# schema.net
KiCad netlist of a schematic drawn in EAGLE
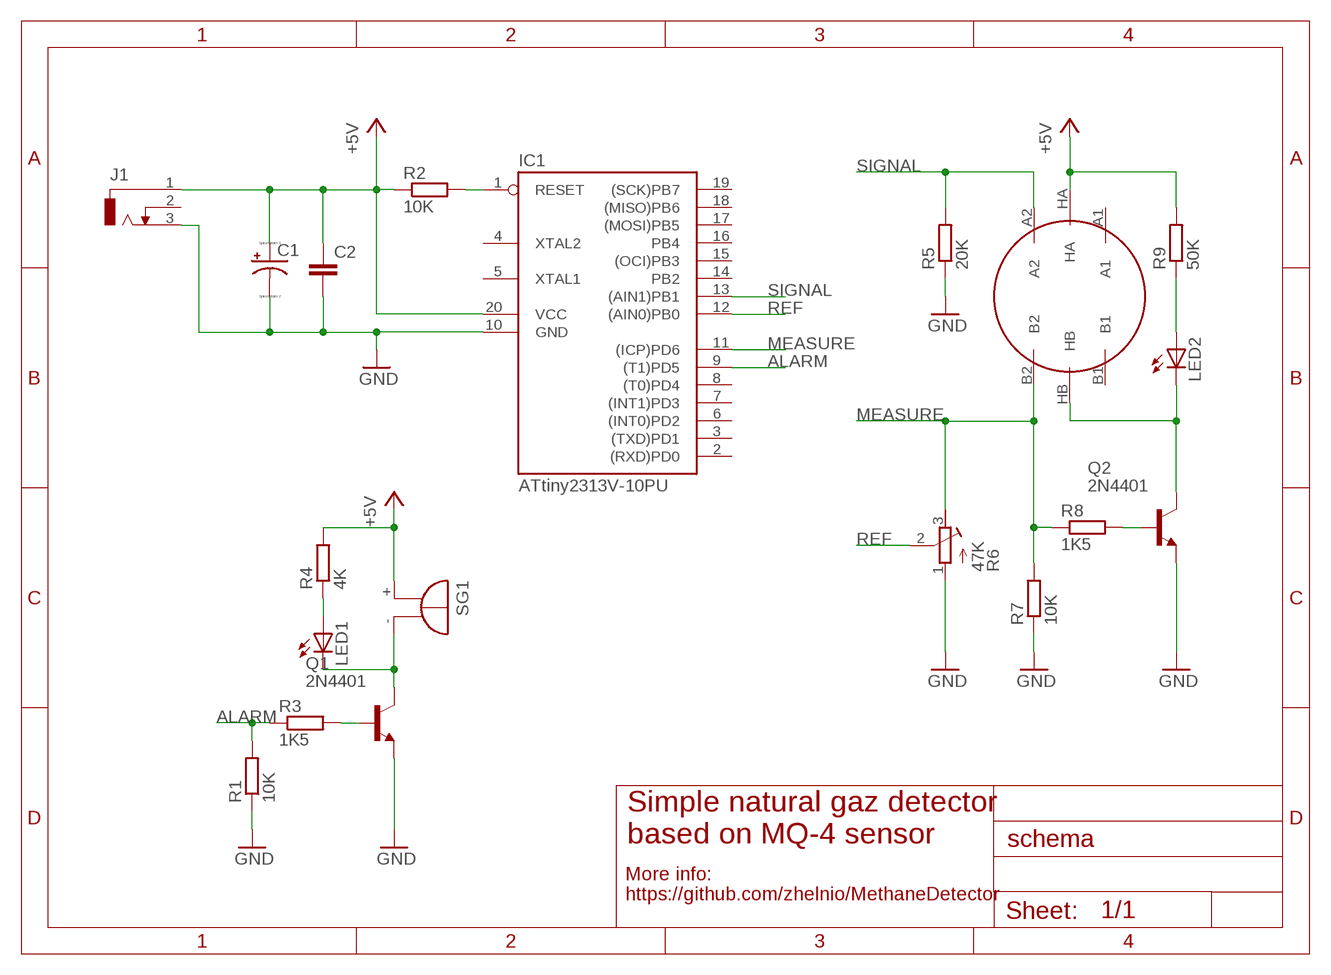
[diagram p0: schematic, sheet 1]

(export (version "E")
  (design (tool "Eeschema 10.0.6"))
  (components
    (comp (ref "C1")
      (value "CPOL-USTT5D9L")
      (footprint "eagle-import:TT5D9L")
      (libsource (lib "eagle-import") (part "CPOL-USTT5D9L"))
    )
    (comp (ref "C2")
      (value "C-EU050-030X075")
      (footprint "eagle-import:C050-030X075")
      (libsource (lib "eagle-import") (part "C-EU050-030X075"))
    )
    (comp (ref "IC1")
      (value "ATtiny2313V-10PU")
      (footprint "eagle-import:DIL20")
      (libsource (lib "eagle-import") (part "AT90S2313P"))
    )
    (comp (ref "J1")
      (value "DCJ0303")
      (footprint "eagle-import:DCJ0303")
      (libsource (lib "eagle-import") (part "DCJ0303"))
    )
    (comp (ref "LED1")
      (value "LED3MM")
      (footprint "eagle-import:LED3MM")
      (libsource (lib "eagle-import") (part "LED3MM"))
    )
    (comp (ref "LED2")
      (value "LED3MM")
      (footprint "eagle-import:LED3MM")
      (libsource (lib "eagle-import") (part "LED3MM"))
    )
    (comp (ref "Q1")
      (value "2N4401")
      (footprint "eagle-import:TO92")
      (libsource (lib "eagle-import") (part "2N3904"))
    )
    (comp (ref "Q2")
      (value "2N4401")
      (footprint "eagle-import:TO92")
      (libsource (lib "eagle-import") (part "2N3904"))
    )
    (comp (ref "R1")
      (value "10K")
      (footprint "eagle-import:0207_10")
      (libsource (lib "eagle-import") (part "R-EU_0207/10"))
    )
    (comp (ref "R2")
      (value "10K")
      (footprint "eagle-import:0204_7")
      (libsource (lib "eagle-import") (part "R-EU_0204/7"))
    )
    (comp (ref "R3")
      (value "1K5")
      (footprint "eagle-import:0207_10")
      (libsource (lib "eagle-import") (part "R-EU_0207/10"))
    )
    (comp (ref "R4")
      (value "4K")
      (footprint "eagle-import:0207_10")
      (libsource (lib "eagle-import") (part "R-EU_0207/10"))
    )
    (comp (ref "R5")
      (value "20K")
      (footprint "eagle-import:0207_10")
      (libsource (lib "eagle-import") (part "R-EU_0207/10"))
    )
    (comp (ref "R6")
      (value "47K")
      (footprint "eagle-import:RTRIM3296W")
      (libsource (lib "eagle-import") (part "R-TRIMM3296W"))
    )
    (comp (ref "R7")
      (value "10K")
      (footprint "eagle-import:0207_10")
      (libsource (lib "eagle-import") (part "R-EU_0207/10"))
    )
    (comp (ref "R8")
      (value "1K5")
      (footprint "eagle-import:0207_10")
      (libsource (lib "eagle-import") (part "R-EU_0207/10"))
    )
    (comp (ref "R9")
      (value "50K")
      (footprint "eagle-import:0207_10")
      (libsource (lib "eagle-import") (part "R-EU_0207/10"))
    )
    (comp (ref "SEN1")
      (value "METHANE_SENSOR")
      (footprint "eagle-import:MQ-3")
      (libsource (lib "eagle-import") (part "METHANE_SENSOR"))
    )
    (comp (ref "SG1")
      (value "BMT1205XH7.5")
      (footprint "eagle-import:BMT1205XH7.5")
      (libsource (lib "eagle-import") (part "BMT1205XH7.5"))
    )
  )
  (nets
    (net (code "1") (name "+5V") (class "Default")
      (node (ref "C1") (pin "+") (pinfunction "+_+") (pintype "passive"))
      (node (ref "C2") (pin "1") (pinfunction "1_1") (pintype "passive"))
      (node (ref "IC1") (pin "20") (pinfunction "VCC_20") (pintype "power_in"))
      (node (ref "J1") (pin "1") (pinfunction "1_1") (pintype "passive"))
      (node (ref "R2") (pin "1") (pinfunction "1_1") (pintype "passive"))
      (node (ref "R4") (pin "2") (pinfunction "2_2") (pintype "passive"))
      (node (ref "R9") (pin "2") (pinfunction "2_2") (pintype "passive"))
      (node (ref "SEN1") (pin "HA") (pinfunction "HA_HA") (pintype "bidirectional"))
      (node (ref "SG1") (pin "+") (pinfunction "+_+") (pintype "passive"))
    )
    (net (code "2") (name "/ALARM") (class "Default")
      (node (ref "IC1") (pin "9") (pinfunction "(T1)PD5_9") (pintype "bidirectional"))
      (node (ref "R1") (pin "2") (pinfunction "2_2") (pintype "passive"))
      (node (ref "R3") (pin "1") (pinfunction "1_1") (pintype "passive"))
    )
    (net (code "3") (name "/MEASURE") (class "Default")
      (node (ref "IC1") (pin "11") (pinfunction "(ICP)PD6_11") (pintype "bidirectional"))
      (node (ref "R6") (pin "3") (pinfunction "E_3") (pintype "passive"))
      (node (ref "R7") (pin "2") (pinfunction "2_2") (pintype "passive"))
      (node (ref "R8") (pin "1") (pinfunction "1_1") (pintype "passive"))
      (node (ref "SEN1") (pin "B2") (pinfunction "B2_B2") (pintype "bidirectional"))
    )
    (net (code "4") (name "/REF") (class "Default")
      (node (ref "IC1") (pin "12") (pinfunction "(AIN0)PB0_12") (pintype "bidirectional"))
      (node (ref "R6") (pin "2") (pinfunction "S_2") (pintype "passive"))
    )
    (net (code "5") (name "/SIGNAL") (class "Default")
      (node (ref "IC1") (pin "13") (pinfunction "(AIN1)PB1_13") (pintype "bidirectional"))
      (node (ref "R5") (pin "2") (pinfunction "2_2") (pintype "passive"))
      (node (ref "SEN1") (pin "A2") (pinfunction "A2_A2") (pintype "bidirectional"))
    )
    (net (code "6") (name "GND") (class "Default")
      (node (ref "C1") (pin "-") (pinfunction "-_-") (pintype "passive"))
      (node (ref "C2") (pin "2") (pinfunction "2_2") (pintype "passive"))
      (node (ref "IC1") (pin "10") (pinfunction "GND_10") (pintype "power_in"))
      (node (ref "J1") (pin "3") (pinfunction "3_3") (pintype "passive"))
      (node (ref "Q1") (pin "3") (pinfunction "E_3") (pintype "passive"))
      (node (ref "Q2") (pin "3") (pinfunction "E_3") (pintype "passive"))
      (node (ref "R1") (pin "1") (pinfunction "1_1") (pintype "passive"))
      (node (ref "R5") (pin "1") (pinfunction "1_1") (pintype "passive"))
      (node (ref "R6") (pin "1") (pinfunction "A_1") (pintype "passive"))
      (node (ref "R7") (pin "1") (pinfunction "1_1") (pintype "passive"))
    )
    (net (code "7") (name "Net-(IC1-RESET)") (class "Default")
      (node (ref "IC1") (pin "1") (pinfunction "RESET_1") (pintype "bidirectional"))
      (node (ref "R2") (pin "2") (pinfunction "2_2") (pintype "passive"))
    )
    (net (code "8") (name "Net-(LED1-C)") (class "Default")
      (node (ref "LED1") (pin "K") (pinfunction "C_K") (pintype "passive"))
      (node (ref "Q1") (pin "1") (pinfunction "C_1") (pintype "passive"))
      (node (ref "SG1") (pin "-") (pinfunction "-_-") (pintype "passive"))
    )
    (net (code "9") (name "Net-(LED1-PadA)") (class "Default")
      (node (ref "LED1") (pin "A") (pinfunction "A_A") (pintype "passive"))
      (node (ref "R4") (pin "1") (pinfunction "1_1") (pintype "passive"))
    )
    (net (code "10") (name "Net-(LED2-C)") (class "Default")
      (node (ref "LED2") (pin "K") (pinfunction "C_K") (pintype "passive"))
      (node (ref "Q2") (pin "1") (pinfunction "C_1") (pintype "passive"))
      (node (ref "SEN1") (pin "HB") (pinfunction "HB_HB") (pintype "bidirectional"))
    )
    (net (code "11") (name "Net-(LED2-PadA)") (class "Default")
      (node (ref "LED2") (pin "A") (pinfunction "A_A") (pintype "passive"))
      (node (ref "R9") (pin "1") (pinfunction "1_1") (pintype "passive"))
    )
    (net (code "12") (name "Net-(Q1-B)") (class "Default")
      (node (ref "Q1") (pin "2") (pinfunction "B_2") (pintype "passive"))
      (node (ref "R3") (pin "2") (pinfunction "2_2") (pintype "passive"))
    )
    (net (code "13") (name "Net-(Q2-B)") (class "Default")
      (node (ref "Q2") (pin "2") (pinfunction "B_2") (pintype "passive"))
      (node (ref "R8") (pin "2") (pinfunction "2_2") (pintype "passive"))
    )
    (net (code "14") (name "unconnected-(IC1-(INT0)PD2-Pad6)") (class "Default")
      (node (ref "IC1") (pin "6") (pinfunction "(INT0)PD2_6") (pintype "bidirectional"))
    )
    (net (code "15") (name "unconnected-(IC1-(INT1)PD3-Pad7)") (class "Default")
      (node (ref "IC1") (pin "7") (pinfunction "(INT1)PD3_7") (pintype "bidirectional"))
    )
    (net (code "16") (name "unconnected-(IC1-(MISO)PB6-Pad18)") (class "Default")
      (node (ref "IC1") (pin "18") (pinfunction "(MISO)PB6_18") (pintype "bidirectional"))
    )
    (net (code "17") (name "unconnected-(IC1-(MOSI)PB5-Pad17)") (class "Default")
      (node (ref "IC1") (pin "17") (pinfunction "(MOSI)PB5_17") (pintype "bidirectional"))
    )
    (net (code "18") (name "unconnected-(IC1-(OCI)PB3-Pad15)") (class "Default")
      (node (ref "IC1") (pin "15") (pinfunction "(OCI)PB3_15") (pintype "bidirectional"))
    )
    (net (code "19") (name "unconnected-(IC1-(RXD)PD0-Pad2)") (class "Default")
      (node (ref "IC1") (pin "2") (pinfunction "(RXD)PD0_2") (pintype "bidirectional"))
    )
    (net (code "20") (name "unconnected-(IC1-(SCK)PB7-Pad19)") (class "Default")
      (node (ref "IC1") (pin "19") (pinfunction "(SCK)PB7_19") (pintype "bidirectional"))
    )
    (net (code "21") (name "unconnected-(IC1-(T0)PD4-Pad8)") (class "Default")
      (node (ref "IC1") (pin "8") (pinfunction "(T0)PD4_8") (pintype "bidirectional"))
    )
    (net (code "22") (name "unconnected-(IC1-(TXD)PD1-Pad3)") (class "Default")
      (node (ref "IC1") (pin "3") (pinfunction "(TXD)PD1_3") (pintype "bidirectional"))
    )
    (net (code "23") (name "unconnected-(IC1-PB2-Pad14)") (class "Default")
      (node (ref "IC1") (pin "14") (pinfunction "PB2_14") (pintype "bidirectional"))
    )
    (net (code "24") (name "unconnected-(IC1-PB4-Pad16)") (class "Default")
      (node (ref "IC1") (pin "16") (pinfunction "PB4_16") (pintype "bidirectional"))
    )
    (net (code "25") (name "unconnected-(IC1-XTAL1-Pad5)") (class "Default")
      (node (ref "IC1") (pin "5") (pinfunction "XTAL1_5") (pintype "bidirectional"))
    )
    (net (code "26") (name "unconnected-(IC1-XTAL2-Pad4)") (class "Default")
      (node (ref "IC1") (pin "4") (pinfunction "XTAL2_4") (pintype "bidirectional"))
    )
    (net (code "27") (name "unconnected-(J1-Pad2)") (class "Default")
      (node (ref "J1") (pin "2") (pinfunction "2_2") (pintype "passive"))
    )
    (net (code "28") (name "unconnected-(SEN1-PadA1)") (class "Default")
      (node (ref "SEN1") (pin "A1") (pinfunction "A1_A1") (pintype "bidirectional"))
    )
    (net (code "29") (name "unconnected-(SEN1-PadB1)") (class "Default")
      (node (ref "SEN1") (pin "B1") (pinfunction "B1_B1") (pintype "bidirectional"))
    )
  )
)
